# Frank-Synced-BLDC-ESC.net
KiCad netlist of a schematic drawn in EAGLE
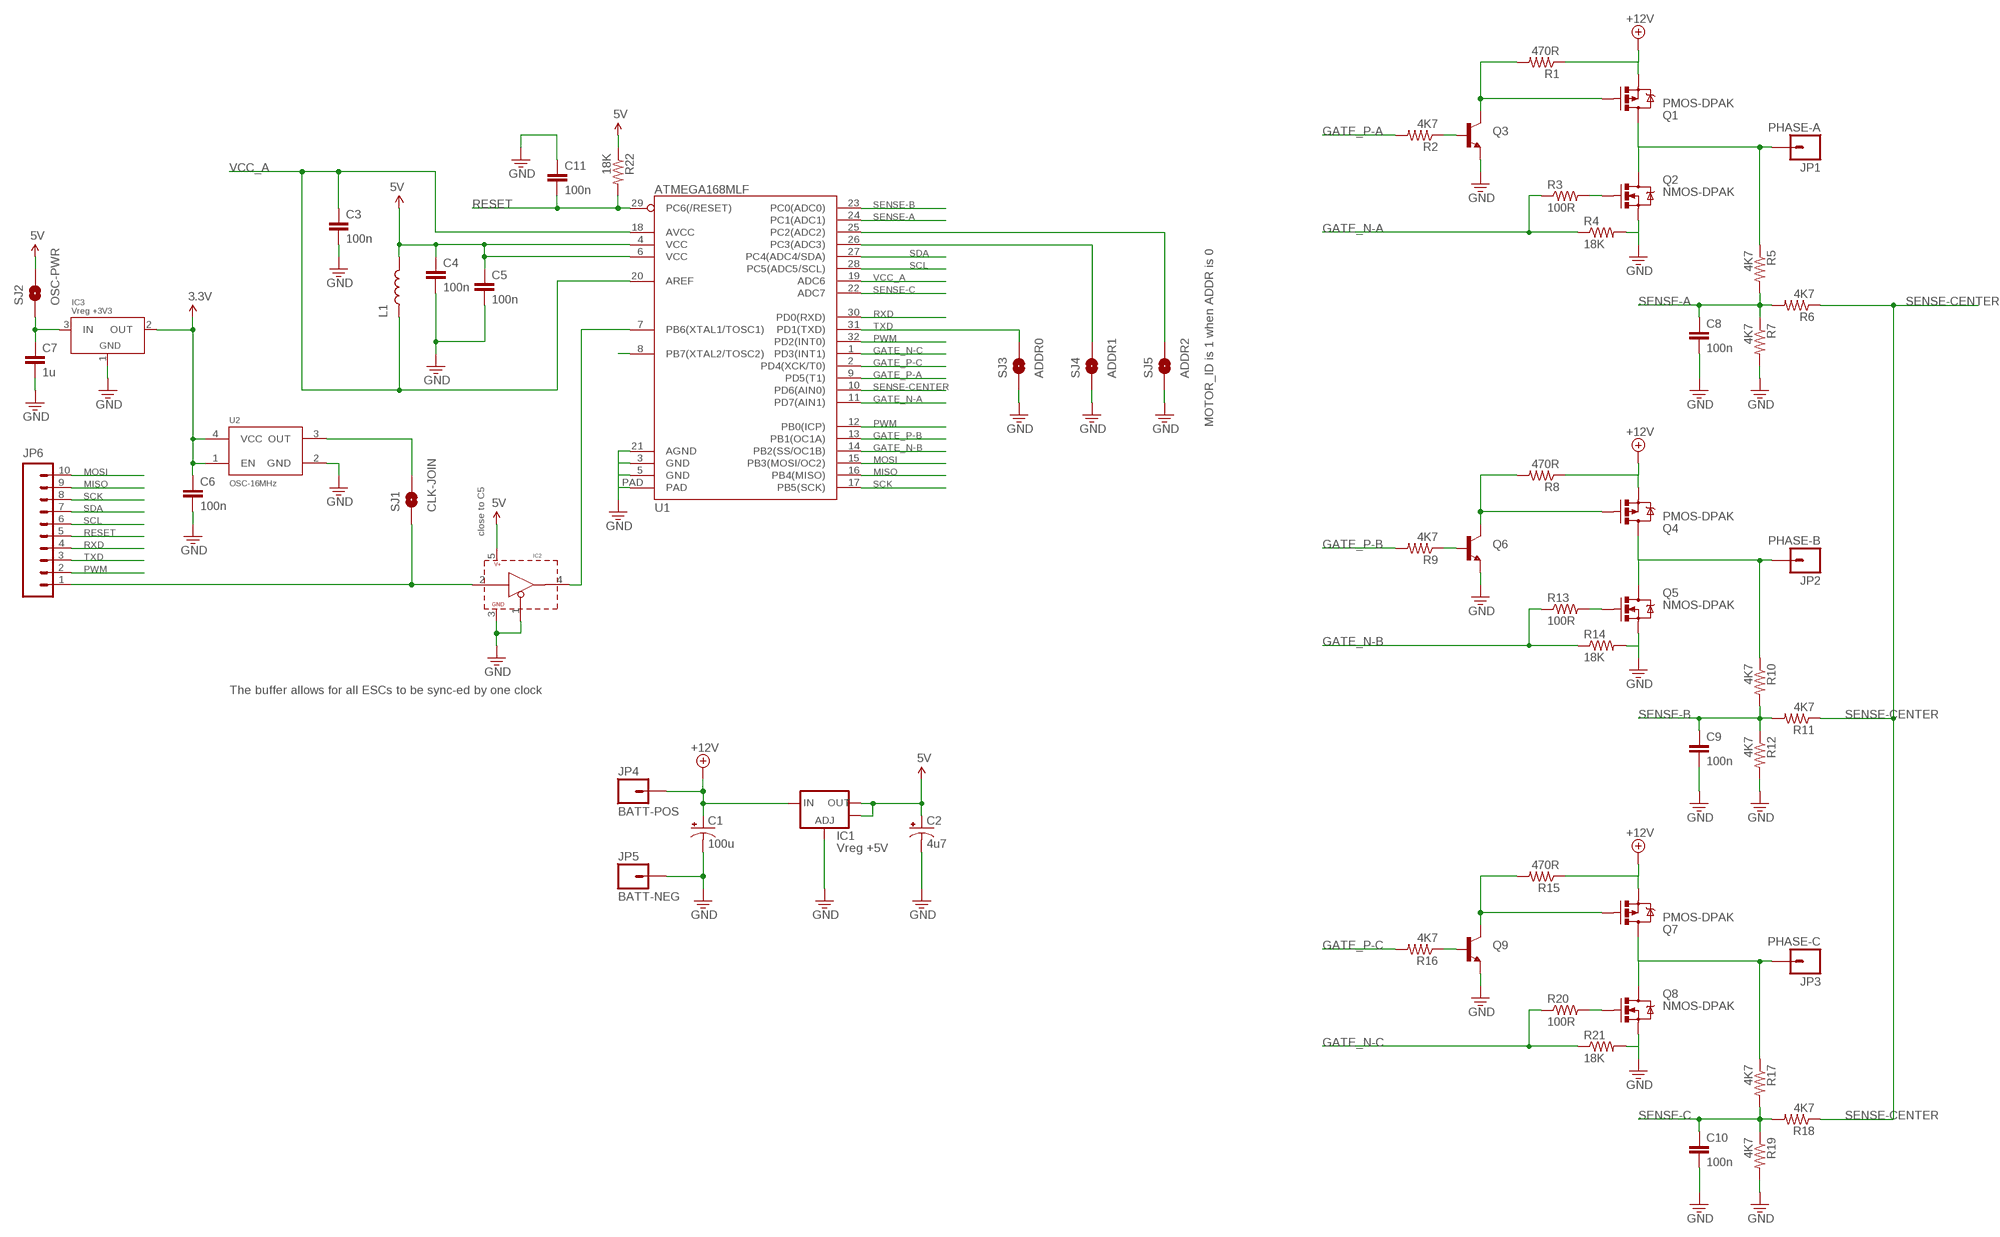
[diagram p0: schematic, sheet 1]

(export (version "E")
  (design (tool "Eeschema 10.0.6"))
  (components
    (comp (ref "C1")
      (value "100u")
      (footprint "eagle-import:CAP-AXIAL-LARGE")
      (libsource (lib "eagle-import") (part "CAP_POL-AXIAL-LARGE"))
    )
    (comp (ref "C2")
      (value "4u7")
      (footprint "eagle-import:EIA3216-KIT")
      (libsource (lib "eagle-import") (part "CAP_POL1206-KIT"))
    )
    (comp (ref "C3")
      (value "100n")
      (footprint "eagle-import:0603-CAP")
      (libsource (lib "eagle-import") (part "CAP0603-CAP"))
    )
    (comp (ref "C4")
      (value "100n")
      (footprint "eagle-import:0603-CAP")
      (libsource (lib "eagle-import") (part "CAP0603-CAP"))
    )
    (comp (ref "C5")
      (value "100n")
      (footprint "eagle-import:0603-CAP")
      (libsource (lib "eagle-import") (part "CAP0603-CAP"))
    )
    (comp (ref "C6")
      (value "100n")
      (footprint "eagle-import:0603-CAP")
      (libsource (lib "eagle-import") (part "CAP0603-CAP"))
    )
    (comp (ref "C7")
      (value "1u")
      (footprint "eagle-import:0603-CAP")
      (libsource (lib "eagle-import") (part "CAP0603-CAP"))
    )
    (comp (ref "C8")
      (value "100n")
      (footprint "eagle-import:0603-CAP")
      (libsource (lib "eagle-import") (part "CAP0603-CAP"))
    )
    (comp (ref "C9")
      (value "100n")
      (footprint "eagle-import:0603-CAP")
      (libsource (lib "eagle-import") (part "CAP0603-CAP"))
    )
    (comp (ref "C10")
      (value "100n")
      (footprint "eagle-import:0603-CAP")
      (libsource (lib "eagle-import") (part "CAP0603-CAP"))
    )
    (comp (ref "C11")
      (value "100n")
      (footprint "eagle-import:0603-CAP")
      (libsource (lib "eagle-import") (part "CAP0603-CAP"))
    )
    (comp (ref "IC1")
      (value "Vreg +5V")
      (footprint "eagle-import:SOT223")
      (libsource (lib "eagle-import") (part "V_REG_LM1117SOT223"))
    )
    (comp (ref "IC2")
      (value "BUFFER-SINGLE-SOT-23-5")
      (footprint "eagle-import:SOT23-5")
      (libsource (lib "eagle-import") (part "BUFFER-SINGLE-SOT-23-5"))
    )
    (comp (ref "IC3")
      (value "Vreg +3V3")
      (footprint "eagle-import:SOT23-3")
      (libsource (lib "eagle-import") (part "V_REG_LDO-SOT23-3"))
    )
    (comp (ref "JP1")
      (value "PHASE-A")
      (footprint "eagle-import:1X1-MOTOR")
      (libsource (lib "eagle-import") (part "M01-MOTORPHASE"))
    )
    (comp (ref "JP2")
      (value "PHASE-B")
      (footprint "eagle-import:1X1-MOTOR")
      (libsource (lib "eagle-import") (part "M01-MOTORPHASE"))
    )
    (comp (ref "JP3")
      (value "PHASE-C")
      (footprint "eagle-import:1X1-MOTOR")
      (libsource (lib "eagle-import") (part "M01-MOTORPHASE"))
    )
    (comp (ref "JP4")
      (value "BATT-POS")
      (footprint "eagle-import:1X1-BATT")
      (libsource (lib "eagle-import") (part "M01-BATT"))
    )
    (comp (ref "JP5")
      (value "BATT-NEG")
      (footprint "eagle-import:1X1-BATT")
      (libsource (lib "eagle-import") (part "M01-BATT"))
    )
    (comp (ref "JP6")
      (value "M10\"")
      (footprint "eagle-import:1X10")
      (libsource (lib "eagle-import") (part "M10{dblquote}"))
    )
    (comp (ref "L1")
      (value "INDUCTOR0603")
      (footprint "eagle-import:0603")
      (libsource (lib "eagle-import") (part "INDUCTOR0603"))
    )
    (comp (ref "Q1")
      (value "PMOS-DPAK")
      (footprint "eagle-import:DPAK")
      (libsource (lib "eagle-import") (part "MOSFET-PCHANNEL-DPAK"))
    )
    (comp (ref "Q2")
      (value "NMOS-DPAK")
      (footprint "eagle-import:DPAK")
      (libsource (lib "eagle-import") (part "MOSFET-NCHANNEL-DPAK"))
    )
    (comp (ref "Q3")
      (value "TRANSISTOR_NPNSOT23-3")
      (footprint "eagle-import:SOT23-3")
      (libsource (lib "eagle-import") (part "TRANSISTOR_NPNSOT23-3"))
    )
    (comp (ref "Q4")
      (value "PMOS-DPAK")
      (footprint "eagle-import:DPAK")
      (libsource (lib "eagle-import") (part "MOSFET-PCHANNEL-DPAK"))
    )
    (comp (ref "Q5")
      (value "NMOS-DPAK")
      (footprint "eagle-import:DPAK")
      (libsource (lib "eagle-import") (part "MOSFET-NCHANNEL-DPAK"))
    )
    (comp (ref "Q6")
      (value "TRANSISTOR_NPNSOT23-3")
      (footprint "eagle-import:SOT23-3")
      (libsource (lib "eagle-import") (part "TRANSISTOR_NPNSOT23-3"))
    )
    (comp (ref "Q7")
      (value "PMOS-DPAK")
      (footprint "eagle-import:DPAK")
      (libsource (lib "eagle-import") (part "MOSFET-PCHANNEL-DPAK"))
    )
    (comp (ref "Q8")
      (value "NMOS-DPAK")
      (footprint "eagle-import:DPAK")
      (libsource (lib "eagle-import") (part "MOSFET-NCHANNEL-DPAK"))
    )
    (comp (ref "Q9")
      (value "TRANSISTOR_NPNSOT23-3")
      (footprint "eagle-import:SOT23-3")
      (libsource (lib "eagle-import") (part "TRANSISTOR_NPNSOT23-3"))
    )
    (comp (ref "R1")
      (value "470R")
      (footprint "eagle-import:0603-RES")
      (libsource (lib "eagle-import") (part "RESISTOR0603-RES"))
    )
    (comp (ref "R2")
      (value "4K7")
      (footprint "eagle-import:0603-RES")
      (libsource (lib "eagle-import") (part "RESISTOR0603-RES"))
    )
    (comp (ref "R3")
      (value "100R")
      (footprint "eagle-import:0603-RES")
      (libsource (lib "eagle-import") (part "RESISTOR0603-RES"))
    )
    (comp (ref "R4")
      (value "18K")
      (footprint "eagle-import:0603-RES")
      (libsource (lib "eagle-import") (part "RESISTOR0603-RES"))
    )
    (comp (ref "R5")
      (value "4K7")
      (footprint "eagle-import:0603-RES")
      (libsource (lib "eagle-import") (part "RESISTOR0603-RES"))
    )
    (comp (ref "R6")
      (value "4K7")
      (footprint "eagle-import:0603-RES")
      (libsource (lib "eagle-import") (part "RESISTOR0603-RES"))
    )
    (comp (ref "R7")
      (value "4K7")
      (footprint "eagle-import:0603-RES")
      (libsource (lib "eagle-import") (part "RESISTOR0603-RES"))
    )
    (comp (ref "R8")
      (value "470R")
      (footprint "eagle-import:0603-RES")
      (libsource (lib "eagle-import") (part "RESISTOR0603-RES"))
    )
    (comp (ref "R9")
      (value "4K7")
      (footprint "eagle-import:0603-RES")
      (libsource (lib "eagle-import") (part "RESISTOR0603-RES"))
    )
    (comp (ref "R10")
      (value "4K7")
      (footprint "eagle-import:0603-RES")
      (libsource (lib "eagle-import") (part "RESISTOR0603-RES"))
    )
    (comp (ref "R11")
      (value "4K7")
      (footprint "eagle-import:0603-RES")
      (libsource (lib "eagle-import") (part "RESISTOR0603-RES"))
    )
    (comp (ref "R12")
      (value "4K7")
      (footprint "eagle-import:0603-RES")
      (libsource (lib "eagle-import") (part "RESISTOR0603-RES"))
    )
    (comp (ref "R13")
      (value "100R")
      (footprint "eagle-import:0603-RES")
      (libsource (lib "eagle-import") (part "RESISTOR0603-RES"))
    )
    (comp (ref "R14")
      (value "18K")
      (footprint "eagle-import:0603-RES")
      (libsource (lib "eagle-import") (part "RESISTOR0603-RES"))
    )
    (comp (ref "R15")
      (value "470R")
      (footprint "eagle-import:0603-RES")
      (libsource (lib "eagle-import") (part "RESISTOR0603-RES"))
    )
    (comp (ref "R16")
      (value "4K7")
      (footprint "eagle-import:0603-RES")
      (libsource (lib "eagle-import") (part "RESISTOR0603-RES"))
    )
    (comp (ref "R17")
      (value "4K7")
      (footprint "eagle-import:0603-RES")
      (libsource (lib "eagle-import") (part "RESISTOR0603-RES"))
    )
    (comp (ref "R18")
      (value "4K7")
      (footprint "eagle-import:0603-RES")
      (libsource (lib "eagle-import") (part "RESISTOR0603-RES"))
    )
    (comp (ref "R19")
      (value "4K7")
      (footprint "eagle-import:0603-RES")
      (libsource (lib "eagle-import") (part "RESISTOR0603-RES"))
    )
    (comp (ref "R20")
      (value "100R")
      (footprint "eagle-import:0603-RES")
      (libsource (lib "eagle-import") (part "RESISTOR0603-RES"))
    )
    (comp (ref "R21")
      (value "18K")
      (footprint "eagle-import:0603-RES")
      (libsource (lib "eagle-import") (part "RESISTOR0603-RES"))
    )
    (comp (ref "R22")
      (value "18K")
      (footprint "eagle-import:0603-RES")
      (libsource (lib "eagle-import") (part "RESISTOR0603-RES"))
    )
    (comp (ref "SJ1")
      (value "CLK-JOIN")
      (footprint "eagle-import:SJ_2S")
      (libsource (lib "eagle-import") (part "SOLDERJUMPERNC"))
    )
    (comp (ref "SJ2")
      (value "OSC-PWR")
      (footprint "eagle-import:SJ_2S")
      (libsource (lib "eagle-import") (part "SOLDERJUMPERNC"))
    )
    (comp (ref "SJ3")
      (value "ADDR0")
      (footprint "eagle-import:SJ_2S-NO")
      (libsource (lib "eagle-import") (part "SOLDERJUMPERNO"))
    )
    (comp (ref "SJ4")
      (value "ADDR1")
      (footprint "eagle-import:SJ_2S-NO")
      (libsource (lib "eagle-import") (part "SOLDERJUMPERNO"))
    )
    (comp (ref "SJ5")
      (value "ADDR2")
      (footprint "eagle-import:SJ_2S-NO")
      (libsource (lib "eagle-import") (part "SOLDERJUMPERNO"))
    )
    (comp (ref "U1")
      (value "ATMEGA168MLF")
      (footprint "eagle-import:MLF32")
      (libsource (lib "eagle-import") (part "ATMEGA168MLF"))
    )
    (comp (ref "U2")
      (value "OSC-16MHz")
      (footprint "eagle-import:OSCILLATOR-2.5X2")
      (libsource (lib "eagle-import") (part "OSCILLATOR-2.5X2"))
    )
  )
  (nets
    (net (code "1") (name "+12V") (class "Default")
      (node (ref "C1") (pin "+") (pinfunction "+_+") (pintype "passive"))
      (node (ref "IC1") (pin "3") (pinfunction "IN_3") (pintype "input"))
      (node (ref "JP4") (pin "P$1") (pinfunction "1_P$1") (pintype "passive"))
      (node (ref "Q1") (pin "3") (pinfunction "S_3") (pintype "passive"))
      (node (ref "Q4") (pin "3") (pinfunction "S_3") (pintype "passive"))
      (node (ref "Q7") (pin "3") (pinfunction "S_3") (pintype "passive"))
      (node (ref "R1") (pin "1") (pinfunction "1_1") (pintype "passive"))
      (node (ref "R15") (pin "1") (pinfunction "1_1") (pintype "passive"))
      (node (ref "R8") (pin "1") (pinfunction "1_1") (pintype "passive"))
    )
    (net (code "2") (name "/GATE_N-A") (class "Default")
      (node (ref "R3") (pin "1") (pinfunction "1_1") (pintype "passive"))
      (node (ref "R4") (pin "1") (pinfunction "1_1") (pintype "passive"))
      (node (ref "U1") (pin "11") (pinfunction "PD7(AIN1)_11") (pintype "bidirectional"))
    )
    (net (code "3") (name "/GATE_N-B") (class "Default")
      (node (ref "R13") (pin "1") (pinfunction "1_1") (pintype "passive"))
      (node (ref "R14") (pin "1") (pinfunction "1_1") (pintype "passive"))
      (node (ref "U1") (pin "14") (pinfunction "PB2(SS/OC1B)_14") (pintype "bidirectional"))
    )
    (net (code "4") (name "/GATE_N-C") (class "Default")
      (node (ref "R20") (pin "1") (pinfunction "1_1") (pintype "passive"))
      (node (ref "R21") (pin "1") (pinfunction "1_1") (pintype "passive"))
      (node (ref "U1") (pin "1") (pinfunction "PD3(INT1)_1") (pintype "bidirectional"))
    )
    (net (code "5") (name "/GATE_P-A") (class "Default")
      (node (ref "R2") (pin "2") (pinfunction "2_2") (pintype "passive"))
      (node (ref "U1") (pin "9") (pinfunction "PD5(T1)_9") (pintype "bidirectional"))
    )
    (net (code "6") (name "/GATE_P-B") (class "Default")
      (node (ref "R9") (pin "2") (pinfunction "2_2") (pintype "passive"))
      (node (ref "U1") (pin "13") (pinfunction "PB1(OC1A)_13") (pintype "bidirectional"))
    )
    (net (code "7") (name "/GATE_P-C") (class "Default")
      (node (ref "R16") (pin "2") (pinfunction "2_2") (pintype "passive"))
      (node (ref "U1") (pin "2") (pinfunction "PD4(XCK/T0)_2") (pintype "bidirectional"))
    )
    (net (code "8") (name "/MISO") (class "Default")
      (node (ref "JP6") (pin "9") (pinfunction "9_9") (pintype "passive"))
      (node (ref "U1") (pin "16") (pinfunction "PB4(MISO)_16") (pintype "bidirectional"))
    )
    (net (code "9") (name "/MOSI") (class "Default")
      (node (ref "JP6") (pin "10") (pinfunction "10_10") (pintype "passive"))
      (node (ref "U1") (pin "15") (pinfunction "PB3(MOSI/OC2)_15") (pintype "bidirectional"))
    )
    (net (code "10") (name "/PWM") (class "Default")
      (node (ref "JP6") (pin "2") (pinfunction "2_2") (pintype "passive"))
      (node (ref "U1") (pin "12") (pinfunction "PB0(ICP)_12") (pintype "bidirectional"))
      (node (ref "U1") (pin "32") (pinfunction "PD2(INT0)_32") (pintype "bidirectional"))
    )
    (net (code "11") (name "/RESET") (class "Default")
      (node (ref "C11") (pin "2") (pinfunction "2_2") (pintype "passive"))
      (node (ref "JP6") (pin "5") (pinfunction "5_5") (pintype "passive"))
      (node (ref "R22") (pin "2") (pinfunction "2_2") (pintype "passive"))
      (node (ref "U1") (pin "29") (pinfunction "PC6(/RESET)_29") (pintype "bidirectional"))
    )
    (net (code "12") (name "/RXD") (class "Default")
      (node (ref "JP6") (pin "4") (pinfunction "4_4") (pintype "passive"))
      (node (ref "U1") (pin "30") (pinfunction "PD0(RXD)_30") (pintype "bidirectional"))
    )
    (net (code "13") (name "/SCK") (class "Default")
      (node (ref "JP6") (pin "8") (pinfunction "8_8") (pintype "passive"))
      (node (ref "U1") (pin "17") (pinfunction "PB5(SCK)_17") (pintype "bidirectional"))
    )
    (net (code "14") (name "/SCL") (class "Default")
      (node (ref "JP6") (pin "6") (pinfunction "6_6") (pintype "passive"))
      (node (ref "U1") (pin "28") (pinfunction "PC5(ADC5/SCL)_28") (pintype "bidirectional"))
    )
    (net (code "15") (name "/SDA") (class "Default")
      (node (ref "JP6") (pin "7") (pinfunction "7_7") (pintype "passive"))
      (node (ref "U1") (pin "27") (pinfunction "PC4(ADC4/SDA)_27") (pintype "bidirectional"))
    )
    (net (code "16") (name "/SENSE-A") (class "Default")
      (node (ref "C8") (pin "1") (pinfunction "1_1") (pintype "passive"))
      (node (ref "R5") (pin "2") (pinfunction "2_2") (pintype "passive"))
      (node (ref "R6") (pin "2") (pinfunction "2_2") (pintype "passive"))
      (node (ref "R7") (pin "1") (pinfunction "1_1") (pintype "passive"))
      (node (ref "U1") (pin "24") (pinfunction "PC1(ADC1)_24") (pintype "bidirectional"))
    )
    (net (code "17") (name "/SENSE-B") (class "Default")
      (node (ref "C9") (pin "1") (pinfunction "1_1") (pintype "passive"))
      (node (ref "R10") (pin "2") (pinfunction "2_2") (pintype "passive"))
      (node (ref "R11") (pin "2") (pinfunction "2_2") (pintype "passive"))
      (node (ref "R12") (pin "1") (pinfunction "1_1") (pintype "passive"))
      (node (ref "U1") (pin "23") (pinfunction "PC0(ADC0)_23") (pintype "bidirectional"))
    )
    (net (code "18") (name "/SENSE-C") (class "Default")
      (node (ref "C10") (pin "1") (pinfunction "1_1") (pintype "passive"))
      (node (ref "R17") (pin "2") (pinfunction "2_2") (pintype "passive"))
      (node (ref "R18") (pin "2") (pinfunction "2_2") (pintype "passive"))
      (node (ref "R19") (pin "1") (pinfunction "1_1") (pintype "passive"))
      (node (ref "U1") (pin "22") (pinfunction "ADC7_22") (pintype "bidirectional"))
    )
    (net (code "19") (name "/SENSE-CENTER") (class "Default")
      (node (ref "R11") (pin "1") (pinfunction "1_1") (pintype "passive"))
      (node (ref "R18") (pin "1") (pinfunction "1_1") (pintype "passive"))
      (node (ref "R6") (pin "1") (pinfunction "1_1") (pintype "passive"))
      (node (ref "U1") (pin "10") (pinfunction "PD6(AIN0)_10") (pintype "bidirectional"))
    )
    (net (code "20") (name "/TXD") (class "Default")
      (node (ref "JP6") (pin "3") (pinfunction "3_3") (pintype "passive"))
      (node (ref "SJ3") (pin "2") (pinfunction "2_2") (pintype "passive"))
      (node (ref "U1") (pin "31") (pinfunction "PD1(TXD)_31") (pintype "bidirectional"))
    )
    (net (code "21") (name "/VCC_A") (class "Default")
      (node (ref "C3") (pin "1") (pinfunction "1_1") (pintype "passive"))
      (node (ref "L1") (pin "1") (pinfunction "1_1") (pintype "passive"))
      (node (ref "U1") (pin "18") (pinfunction "AVCC_18") (pintype "bidirectional"))
      (node (ref "U1") (pin "19") (pinfunction "ADC6_19") (pintype "bidirectional"))
      (node (ref "U1") (pin "20") (pinfunction "AREF_20") (pintype "bidirectional"))
    )
    (net (code "22") (name "3.3V") (class "Default")
      (node (ref "C6") (pin "1") (pinfunction "1_1") (pintype "passive"))
      (node (ref "IC3") (pin "2") (pinfunction "OUT_2") (pintype "bidirectional"))
      (node (ref "U2") (pin "1") (pinfunction "EN_1") (pintype "bidirectional"))
      (node (ref "U2") (pin "4") (pinfunction "VCC_4") (pintype "bidirectional"))
    )
    (net (code "23") (name "5V") (class "Default")
      (node (ref "C2") (pin "A") (pinfunction "+_A") (pintype "passive"))
      (node (ref "C4") (pin "1") (pinfunction "1_1") (pintype "passive"))
      (node (ref "C5") (pin "1") (pinfunction "1_1") (pintype "passive"))
      (node (ref "IC1") (pin "2") (pinfunction "OUT_2") (pintype "output"))
      (node (ref "IC1") (pin "4") (pinfunction "OUT_4") (pintype "output"))
      (node (ref "IC2") (pin "5") (pinfunction "V+_5") (pintype "power_in"))
      (node (ref "L1") (pin "2") (pinfunction "2_2") (pintype "passive"))
      (node (ref "R22") (pin "1") (pinfunction "1_1") (pintype "passive"))
      (node (ref "SJ2") (pin "2") (pinfunction "2_2") (pintype "passive"))
      (node (ref "U1") (pin "4") (pinfunction "VCC_4") (pintype "bidirectional"))
      (node (ref "U1") (pin "6") (pinfunction "VCC_6") (pintype "bidirectional"))
    )
    (net (code "24") (name "GND") (class "Default")
      (node (ref "C1") (pin "-") (pinfunction "-_-") (pintype "passive"))
      (node (ref "C10") (pin "2") (pinfunction "2_2") (pintype "passive"))
      (node (ref "C11") (pin "1") (pinfunction "1_1") (pintype "passive"))
      (node (ref "C2") (pin "C") (pinfunction "-_C") (pintype "passive"))
      (node (ref "C3") (pin "2") (pinfunction "2_2") (pintype "passive"))
      (node (ref "C4") (pin "2") (pinfunction "2_2") (pintype "passive"))
      (node (ref "C5") (pin "2") (pinfunction "2_2") (pintype "passive"))
      (node (ref "C6") (pin "2") (pinfunction "2_2") (pintype "passive"))
      (node (ref "C7") (pin "2") (pinfunction "2_2") (pintype "passive"))
      (node (ref "C8") (pin "2") (pinfunction "2_2") (pintype "passive"))
      (node (ref "C9") (pin "2") (pinfunction "2_2") (pintype "passive"))
      (node (ref "IC1") (pin "1") (pinfunction "ADJ_1") (pintype "input"))
      (node (ref "IC2") (pin "1") (pinfunction "~{OE}_1") (pintype "input"))
      (node (ref "IC2") (pin "3") (pinfunction "GND_3") (pintype "power_in"))
      (node (ref "IC3") (pin "1") (pinfunction "GND_1") (pintype "bidirectional"))
      (node (ref "JP5") (pin "P$1") (pinfunction "1_P$1") (pintype "passive"))
      (node (ref "Q2") (pin "3") (pinfunction "S_3") (pintype "passive"))
      (node (ref "Q3") (pin "2") (pinfunction "E_2") (pintype "passive"))
      (node (ref "Q5") (pin "3") (pinfunction "S_3") (pintype "passive"))
      (node (ref "Q6") (pin "2") (pinfunction "E_2") (pintype "passive"))
      (node (ref "Q8") (pin "3") (pinfunction "S_3") (pintype "passive"))
      (node (ref "Q9") (pin "2") (pinfunction "E_2") (pintype "passive"))
      (node (ref "R12") (pin "2") (pinfunction "2_2") (pintype "passive"))
      (node (ref "R14") (pin "2") (pinfunction "2_2") (pintype "passive"))
      (node (ref "R19") (pin "2") (pinfunction "2_2") (pintype "passive"))
      (node (ref "R21") (pin "2") (pinfunction "2_2") (pintype "passive"))
      (node (ref "R4") (pin "2") (pinfunction "2_2") (pintype "passive"))
      (node (ref "R7") (pin "2") (pinfunction "2_2") (pintype "passive"))
      (node (ref "SJ3") (pin "1") (pinfunction "1_1") (pintype "passive"))
      (node (ref "SJ4") (pin "1") (pinfunction "1_1") (pintype "passive"))
      (node (ref "SJ5") (pin "1") (pinfunction "1_1") (pintype "passive"))
      (node (ref "U1") (pin "21") (pinfunction "AGND_21") (pintype "bidirectional"))
      (node (ref "U1") (pin "3") (pinfunction "GND_3") (pintype "bidirectional"))
      (node (ref "U1") (pin "5") (pinfunction "GND_5") (pintype "bidirectional"))
      (node (ref "U1") (pin "PAD") (pinfunction "PAD_PAD") (pintype "bidirectional"))
      (node (ref "U2") (pin "2") (pinfunction "GND_2") (pintype "bidirectional"))
    )
    (net (code "25") (name "Net-(IC2-IN)") (class "Default")
      (node (ref "IC2") (pin "2") (pinfunction "IN_2") (pintype "input"))
      (node (ref "JP6") (pin "1") (pinfunction "1_1") (pintype "passive"))
      (node (ref "SJ1") (pin "1") (pinfunction "1_1") (pintype "passive"))
    )
    (net (code "26") (name "Net-(IC2-OUT)") (class "Default")
      (node (ref "IC2") (pin "4") (pinfunction "OUT_4") (pintype "output"))
      (node (ref "U1") (pin "7") (pinfunction "PB6(XTAL1/TOSC1)_7") (pintype "bidirectional"))
    )
    (net (code "27") (name "Net-(IC3-IN)") (class "Default")
      (node (ref "C7") (pin "1") (pinfunction "1_1") (pintype "passive"))
      (node (ref "IC3") (pin "3") (pinfunction "IN_3") (pintype "bidirectional"))
      (node (ref "SJ2") (pin "1") (pinfunction "1_1") (pintype "passive"))
    )
    (net (code "28") (name "Net-(JP1-1)") (class "Default")
      (node (ref "JP1") (pin "P$1") (pinfunction "1_P$1") (pintype "passive"))
      (node (ref "Q1") (pin "4") (pinfunction "D_4") (pintype "passive"))
      (node (ref "Q2") (pin "4") (pinfunction "D_4") (pintype "passive"))
      (node (ref "R5") (pin "1") (pinfunction "1_1") (pintype "passive"))
    )
    (net (code "29") (name "Net-(JP2-1)") (class "Default")
      (node (ref "JP2") (pin "P$1") (pinfunction "1_P$1") (pintype "passive"))
      (node (ref "Q4") (pin "4") (pinfunction "D_4") (pintype "passive"))
      (node (ref "Q5") (pin "4") (pinfunction "D_4") (pintype "passive"))
      (node (ref "R10") (pin "1") (pinfunction "1_1") (pintype "passive"))
    )
    (net (code "30") (name "Net-(JP3-1)") (class "Default")
      (node (ref "JP3") (pin "P$1") (pinfunction "1_P$1") (pintype "passive"))
      (node (ref "Q7") (pin "4") (pinfunction "D_4") (pintype "passive"))
      (node (ref "Q8") (pin "4") (pinfunction "D_4") (pintype "passive"))
      (node (ref "R17") (pin "1") (pinfunction "1_1") (pintype "passive"))
    )
    (net (code "31") (name "Net-(Q1-G)") (class "Default")
      (node (ref "Q1") (pin "1") (pinfunction "G_1") (pintype "passive"))
      (node (ref "Q3") (pin "3") (pinfunction "C_3") (pintype "passive"))
      (node (ref "R1") (pin "2") (pinfunction "2_2") (pintype "passive"))
    )
    (net (code "32") (name "Net-(Q2-G)") (class "Default")
      (node (ref "Q2") (pin "1") (pinfunction "G_1") (pintype "passive"))
      (node (ref "R3") (pin "2") (pinfunction "2_2") (pintype "passive"))
    )
    (net (code "33") (name "Net-(Q3-B)") (class "Default")
      (node (ref "Q3") (pin "1") (pinfunction "B_1") (pintype "passive"))
      (node (ref "R2") (pin "1") (pinfunction "1_1") (pintype "passive"))
    )
    (net (code "34") (name "Net-(Q4-G)") (class "Default")
      (node (ref "Q4") (pin "1") (pinfunction "G_1") (pintype "passive"))
      (node (ref "Q6") (pin "3") (pinfunction "C_3") (pintype "passive"))
      (node (ref "R8") (pin "2") (pinfunction "2_2") (pintype "passive"))
    )
    (net (code "35") (name "Net-(Q5-G)") (class "Default")
      (node (ref "Q5") (pin "1") (pinfunction "G_1") (pintype "passive"))
      (node (ref "R13") (pin "2") (pinfunction "2_2") (pintype "passive"))
    )
    (net (code "36") (name "Net-(Q6-B)") (class "Default")
      (node (ref "Q6") (pin "1") (pinfunction "B_1") (pintype "passive"))
      (node (ref "R9") (pin "1") (pinfunction "1_1") (pintype "passive"))
    )
    (net (code "37") (name "Net-(Q7-G)") (class "Default")
      (node (ref "Q7") (pin "1") (pinfunction "G_1") (pintype "passive"))
      (node (ref "Q9") (pin "3") (pinfunction "C_3") (pintype "passive"))
      (node (ref "R15") (pin "2") (pinfunction "2_2") (pintype "passive"))
    )
    (net (code "38") (name "Net-(Q8-G)") (class "Default")
      (node (ref "Q8") (pin "1") (pinfunction "G_1") (pintype "passive"))
      (node (ref "R20") (pin "2") (pinfunction "2_2") (pintype "passive"))
    )
    (net (code "39") (name "Net-(Q9-B)") (class "Default")
      (node (ref "Q9") (pin "1") (pinfunction "B_1") (pintype "passive"))
      (node (ref "R16") (pin "1") (pinfunction "1_1") (pintype "passive"))
    )
    (net (code "40") (name "Net-(U1-PC2(ADC2))") (class "Default")
      (node (ref "SJ5") (pin "2") (pinfunction "2_2") (pintype "passive"))
      (node (ref "U1") (pin "25") (pinfunction "PC2(ADC2)_25") (pintype "bidirectional"))
    )
    (net (code "41") (name "Net-(U1-PC3(ADC3))") (class "Default")
      (node (ref "SJ4") (pin "2") (pinfunction "2_2") (pintype "passive"))
      (node (ref "U1") (pin "26") (pinfunction "PC3(ADC3)_26") (pintype "bidirectional"))
    )
    (net (code "42") (name "Net-(U2-OUT)") (class "Default")
      (node (ref "SJ1") (pin "2") (pinfunction "2_2") (pintype "passive"))
      (node (ref "U2") (pin "3") (pinfunction "OUT_3") (pintype "bidirectional"))
    )
    (net (code "43") (name "unconnected-(U1-PB7(XTAL2{slash}TOSC2)-Pad8)") (class "Default")
      (node (ref "U1") (pin "8") (pinfunction "PB7(XTAL2/TOSC2)_8") (pintype "bidirectional"))
    )
  )
)
